# SCH_My-C51_2025-06-27.net
KiCad netlist of a schematic drawn in EasyEDA
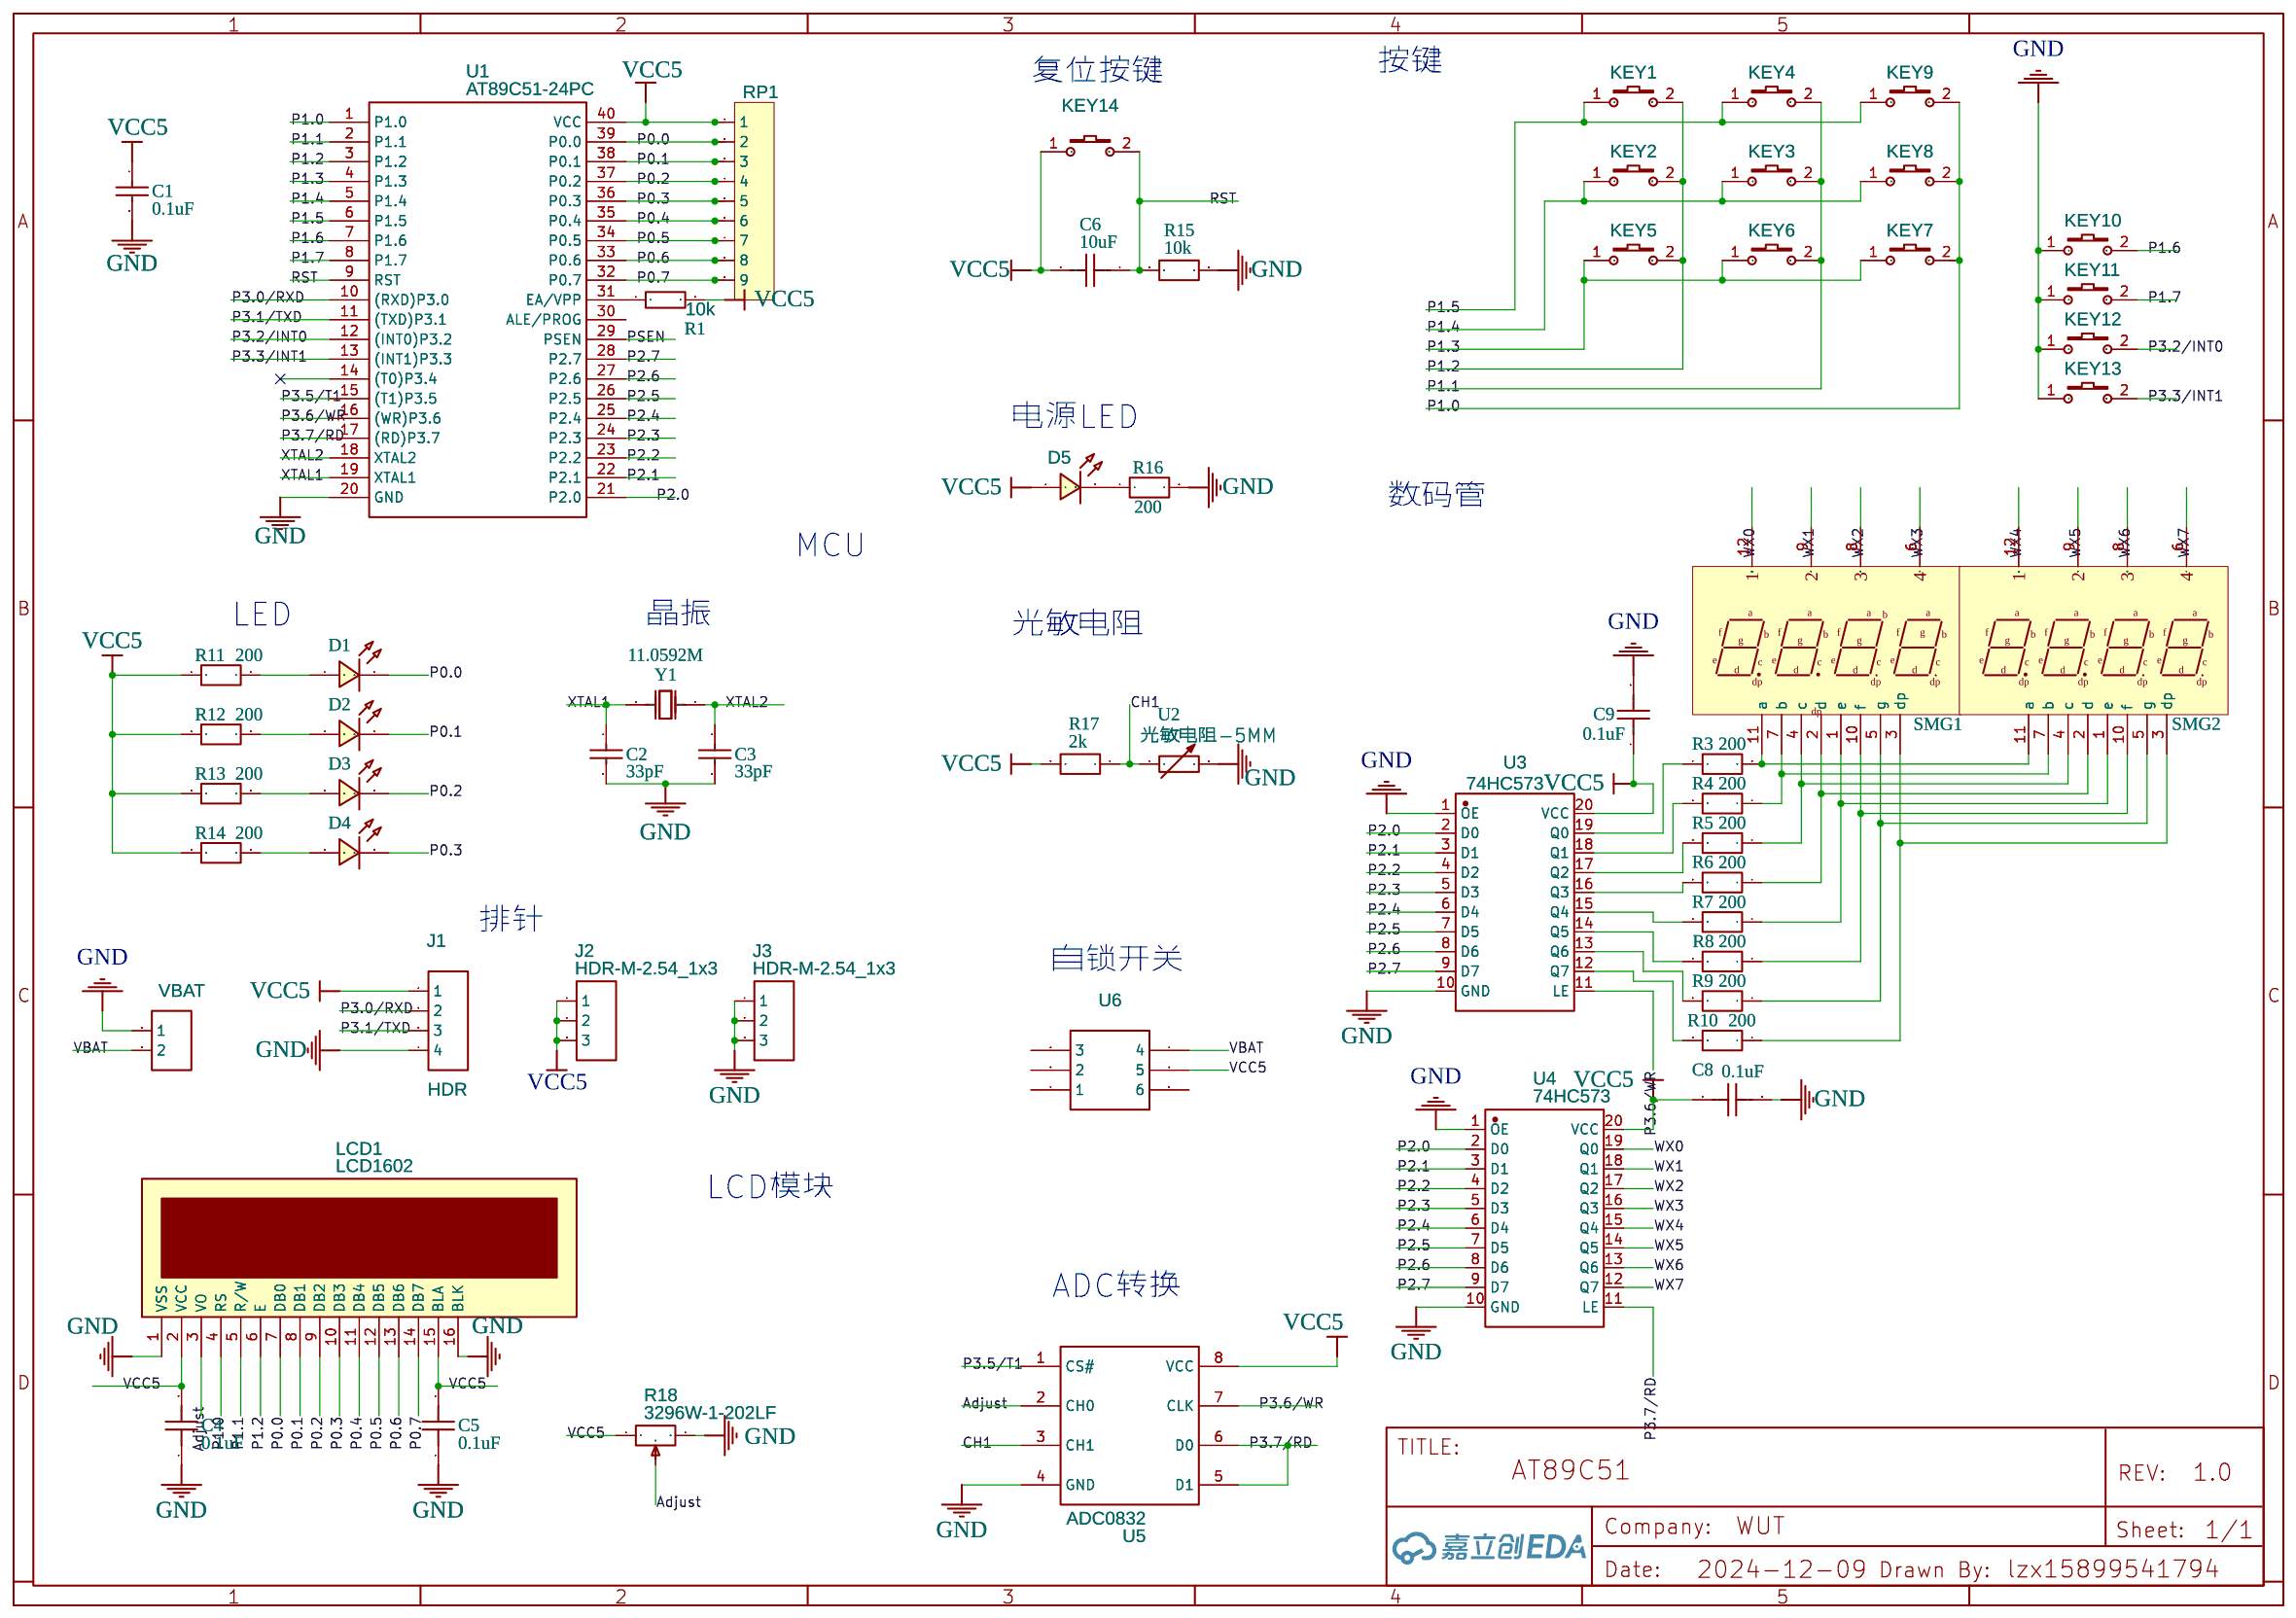
[diagram p0: schematic sheet]

(export (version "E")
  (design (tool "Eeschema 10.0.6"))
  (components
    (comp (ref "C1")
      (value "0.1uF")
      (fields
        (field (name "Manufacturer Part") "C0201X6S104K6R3NTA")
        (field (name "Manufacturer") "EYANG(宇阳科技)")
      )
      (libsource (lib "") (part "C0201X6S104K6R3NTA"))
    )
    (comp (ref "C2")
      (value "33pF")
      (fields (field (name "Manufacturer Part") "CGA2B2C0G1H330JT0Y0F") (field (name "Manufacturer") "TDK"))
      (libsource (lib "") (part "CGA2B2C0G1H330JT0Y0F"))
    )
    (comp (ref "C3")
      (value "33pF")
      (fields (field (name "Manufacturer Part") "CGA2B2C0G1H330JT0Y0F") (field (name "Manufacturer") "TDK"))
      (libsource (lib "") (part "CGA2B2C0G1H330JT0Y0F"))
    )
    (comp (ref "C4") (value "0.1uF") (libsource (lib "") (part "C_0603_US")))
    (comp (ref "C5") (value "0.1uF") (libsource (lib "") (part "C_0603_US")))
    (comp (ref "C6") (value "10uF") (libsource (lib "") (part "C_0603_US_1")))
    (comp (ref "C8") (value "0.1uF") (libsource (lib "") (part "C_0603_US_2")))
    (comp (ref "C9") (value "0.1uF") (libsource (lib "") (part "C_0603_US")))
    (comp (ref "D1")
      (value "LED-0603_R")
      (fields
        (field (name "Manufacturer Part") "19-217/R6C-AL1M2VY/3T")
        (field (name "Manufacturer") "EVERLIGHT(台湾亿光)")
      )
      (libsource (lib "") (part "LED-0603_R"))
    )
    (comp (ref "D2")
      (value "LED-0603_R")
      (fields
        (field (name "Manufacturer Part") "19-217/R6C-AL1M2VY/3T")
        (field (name "Manufacturer") "EVERLIGHT(台湾亿光)")
      )
      (libsource (lib "") (part "LED-0603_R"))
    )
    (comp (ref "D3")
      (value "LED-0603_R")
      (fields
        (field (name "Manufacturer Part") "19-217/R6C-AL1M2VY/3T")
        (field (name "Manufacturer") "EVERLIGHT(台湾亿光)")
      )
      (libsource (lib "") (part "LED-0603_R"))
    )
    (comp (ref "D4")
      (value "LED-0603_R")
      (fields
        (field (name "Manufacturer Part") "19-217/R6C-AL1M2VY/3T")
        (field (name "Manufacturer") "EVERLIGHT(台湾亿光)")
      )
      (libsource (lib "") (part "LED-0603_R"))
    )
    (comp (ref "D5")
      (value "LED-0603_R")
      (fields
        (field (name "Manufacturer Part") "19-217/R6C-AL1M2VY/3T")
        (field (name "Manufacturer") "EVERLIGHT(台湾亿光)")
      )
      (libsource (lib "") (part "LED-0603_R"))
    )
    (comp (ref "J1") (value "HDR") (libsource (lib "") (part "HDR-M-2.54_1x4")))
    (comp (ref "J2") (value "HDR-M-2.54_1x3") (libsource (lib "") (part "HDR-M-2.54_1x3")))
    (comp (ref "J3") (value "HDR-M-2.54_1x3") (libsource (lib "") (part "HDR-M-2.54_1x3")))
    (comp (ref "KEY1")
      (value "K2-3.6×6.1_SMD")
      (fields (field (name "Manufacturer Part") "K2-1107ST-A4SW-06"))
      (libsource (lib "") (part "K2-3.6×6.1_SMD"))
    )
    (comp (ref "KEY2")
      (value "K2-3.6×6.1_SMD")
      (fields (field (name "Manufacturer Part") "K2-1107ST-A4SW-06"))
      (libsource (lib "") (part "K2-3.6×6.1_SMD"))
    )
    (comp (ref "KEY3")
      (value "K2-3.6×6.1_SMD")
      (fields (field (name "Manufacturer Part") "K2-1107ST-A4SW-06"))
      (libsource (lib "") (part "K2-3.6×6.1_SMD"))
    )
    (comp (ref "KEY4")
      (value "K2-3.6×6.1_SMD")
      (fields (field (name "Manufacturer Part") "K2-1107ST-A4SW-06"))
      (libsource (lib "") (part "K2-3.6×6.1_SMD"))
    )
    (comp (ref "KEY5")
      (value "K2-3.6×6.1_SMD")
      (fields (field (name "Manufacturer Part") "K2-1107ST-A4SW-06"))
      (libsource (lib "") (part "K2-3.6×6.1_SMD"))
    )
    (comp (ref "KEY6")
      (value "K2-3.6×6.1_SMD")
      (fields (field (name "Manufacturer Part") "K2-1107ST-A4SW-06"))
      (libsource (lib "") (part "K2-3.6×6.1_SMD"))
    )
    (comp (ref "KEY7")
      (value "K2-3.6×6.1_SMD")
      (fields (field (name "Manufacturer Part") "K2-1107ST-A4SW-06"))
      (libsource (lib "") (part "K2-3.6×6.1_SMD"))
    )
    (comp (ref "KEY8")
      (value "K2-3.6×6.1_SMD")
      (fields (field (name "Manufacturer Part") "K2-1107ST-A4SW-06"))
      (libsource (lib "") (part "K2-3.6×6.1_SMD"))
    )
    (comp (ref "KEY9")
      (value "K2-3.6×6.1_SMD")
      (fields (field (name "Manufacturer Part") "K2-1107ST-A4SW-06"))
      (libsource (lib "") (part "K2-3.6×6.1_SMD"))
    )
    (comp (ref "KEY10")
      (value "K2-3.6×6.1_SMD")
      (fields (field (name "Manufacturer Part") "K2-1107ST-A4SW-06"))
      (libsource (lib "") (part "K2-3.6×6.1_SMD"))
    )
    (comp (ref "KEY11")
      (value "K2-3.6×6.1_SMD")
      (fields (field (name "Manufacturer Part") "K2-1107ST-A4SW-06"))
      (libsource (lib "") (part "K2-3.6×6.1_SMD"))
    )
    (comp (ref "KEY12")
      (value "K2-3.6×6.1_SMD")
      (fields (field (name "Manufacturer Part") "K2-1107ST-A4SW-06"))
      (libsource (lib "") (part "K2-3.6×6.1_SMD"))
    )
    (comp (ref "KEY13")
      (value "K2-3.6×6.1_SMD")
      (fields (field (name "Manufacturer Part") "K2-1107ST-A4SW-06"))
      (libsource (lib "") (part "K2-3.6×6.1_SMD"))
    )
    (comp (ref "KEY14")
      (value "K2-3.6×6.1_SMD")
      (fields (field (name "Manufacturer Part") "K2-1107ST-A4SW-06"))
      (libsource (lib "") (part "K2-3.6×6.1_SMD"))
    )
    (comp (ref "LCD1")
      (value "LCD1602")
      (fields
        (field (name "Manufacturer Part") "LCM1602K-NSW-BBW")
        (field (name "Manufacturer") "LONTECH(厦门龙特)")
      )
      (libsource (lib "") (part "LCD1602"))
    )
    (comp (ref "P11") (value "SMG2") (libsource (lib "") (part "0.36-4位数码管")))
    (comp (ref "P12") (value "SMG1") (libsource (lib "") (part "0.36-4位数码管_1")))
    (comp (ref "R1")
      (value "10k")
      (fields (field (name "Manufacturer Part") "RK73H1JTTD1052F") (field (name "Manufacturer") "KOA"))
      (libsource (lib "") (part "RK73H1JTTD1052F"))
    )
    (comp (ref "R3") (value "200") (libsource (lib "") (part "R_0603_EU")))
    (comp (ref "R4") (value "200") (libsource (lib "") (part "R_0603_EU_1")))
    (comp (ref "R5") (value "200") (libsource (lib "") (part "R_0603_EU_1")))
    (comp (ref "R6") (value "200") (libsource (lib "") (part "R_0603_EU_1")))
    (comp (ref "R7") (value "200") (libsource (lib "") (part "R_0603_EU_1")))
    (comp (ref "R8") (value "200") (libsource (lib "") (part "R_0603_EU_1")))
    (comp (ref "R9") (value "200") (libsource (lib "") (part "R_0603_EU_1")))
    (comp (ref "R10") (value "200") (libsource (lib "") (part "R_0603_EU_1")))
    (comp (ref "R11") (value "200") (libsource (lib "") (part "R_0603_EU")))
    (comp (ref "R12") (value "200") (libsource (lib "") (part "R_0603_EU")))
    (comp (ref "R13") (value "200") (libsource (lib "") (part "R_0603_EU")))
    (comp (ref "R14") (value "200") (libsource (lib "") (part "R_0603_EU")))
    (comp (ref "R15") (value "10k") (libsource (lib "") (part "R_0603_EU_1")))
    (comp (ref "R16") (value "200") (libsource (lib "") (part "R_0603_EU")))
    (comp (ref "R17") (value "2k") (libsource (lib "") (part "R_0603_EU_1")))
    (comp (ref "R18")
      (value "3296W-1-202LF")
      (fields (field (name "Manufacturer") "Bochen"))
      (libsource (lib "") (part "3296W-1-202LF_C118206 copy"))
    )
    (comp (ref "RP1") (value "排阻") (libsource (lib "") (part "排阻")))
    (comp (ref "U1") (value "AT89C51-24PC") (libsource (lib "") (part "AT89C51-24PC")))
    (comp (ref "U2") (value "光敏电阻-5MM") (libsource (lib "") (part "光敏电阻-5MM")))
    (comp (ref "U3")
      (value "74HC573")
      (fields
        (field (name "Manufacturer Part") "MC74HC573ADWR2G")
        (field (name "Manufacturer") "onsemi(安森美)")
      )
      (libsource (lib "") (part "74HC573"))
    )
    (comp (ref "U4")
      (value "74HC573")
      (fields
        (field (name "Manufacturer Part") "MC74HC573ADWR2G")
        (field (name "Manufacturer") "onsemi(安森美)")
      )
      (libsource (lib "") (part "74HC573"))
    )
    (comp (ref "U5") (value "ADC0832") (libsource (lib "") (part "ADC0832")))
    (comp (ref "U6") (value "自锁开关7*7") (libsource (lib "") (part "自锁开关7*7")))
    (comp (ref "VBAT") (value "端子") (libsource (lib "") (part "CONN-TH_2P-P5.00")))
    (comp (ref "Y1") (value "11.0592M") (libsource (lib "") (part "晶振")))
  )
  (nets
    (net (code "1") (name "/Adjust") (class "Default")
      (node (ref "LCD1") (pin "3") (pinfunction "VO_3") (pintype "unspecified"))
      (node (ref "R18") (pin "2") (pinfunction "2_2") (pintype "input"))
      (node (ref "U5") (pin "2") (pinfunction "CH0_2") (pintype "unspecified"))
    )
    (net (code "2") (name "/CH1") (class "Default")
      (node (ref "R17") (pin "1") (pinfunction "1_1") (pintype "unspecified"))
      (node (ref "U2") (pin "1") (pinfunction "1_1") (pintype "unspecified"))
      (node (ref "U5") (pin "3") (pinfunction "CH1_3") (pintype "unspecified"))
    )
    (net (code "3") (name "/P0.0") (class "Default")
      (node (ref "D1") (pin "2") (pinfunction "2_2") (pintype "unspecified"))
      (node (ref "LCD1") (pin "7") (pinfunction "DB0_7") (pintype "unspecified"))
      (node (ref "RP1") (pin "2") (pinfunction "2_2") (pintype "unspecified"))
      (node (ref "U1") (pin "39") (pinfunction "P0.0_39") (pintype "unspecified"))
    )
    (net (code "4") (name "/P0.1") (class "Default")
      (node (ref "D2") (pin "2") (pinfunction "2_2") (pintype "unspecified"))
      (node (ref "LCD1") (pin "8") (pinfunction "DB1_8") (pintype "unspecified"))
      (node (ref "RP1") (pin "3") (pinfunction "3_3") (pintype "unspecified"))
      (node (ref "U1") (pin "38") (pinfunction "P0.1_38") (pintype "unspecified"))
    )
    (net (code "5") (name "/P0.2") (class "Default")
      (node (ref "D3") (pin "2") (pinfunction "2_2") (pintype "unspecified"))
      (node (ref "LCD1") (pin "9") (pinfunction "DB2_9") (pintype "unspecified"))
      (node (ref "RP1") (pin "4") (pinfunction "4_4") (pintype "unspecified"))
      (node (ref "U1") (pin "37") (pinfunction "P0.2_37") (pintype "unspecified"))
    )
    (net (code "6") (name "/P0.3") (class "Default")
      (node (ref "D4") (pin "2") (pinfunction "2_2") (pintype "unspecified"))
      (node (ref "LCD1") (pin "10") (pinfunction "DB3_10") (pintype "unspecified"))
      (node (ref "RP1") (pin "5") (pinfunction "5_5") (pintype "unspecified"))
      (node (ref "U1") (pin "36") (pinfunction "P0.3_36") (pintype "unspecified"))
    )
    (net (code "7") (name "/P0.4") (class "Default")
      (node (ref "LCD1") (pin "11") (pinfunction "DB4_11") (pintype "unspecified"))
      (node (ref "RP1") (pin "6") (pinfunction "6_6") (pintype "unspecified"))
      (node (ref "U1") (pin "35") (pinfunction "P0.4_35") (pintype "unspecified"))
    )
    (net (code "8") (name "/P0.5") (class "Default")
      (node (ref "LCD1") (pin "12") (pinfunction "DB5_12") (pintype "unspecified"))
      (node (ref "RP1") (pin "7") (pinfunction "7_7") (pintype "unspecified"))
      (node (ref "U1") (pin "34") (pinfunction "P0.5_34") (pintype "unspecified"))
    )
    (net (code "9") (name "/P0.6") (class "Default")
      (node (ref "LCD1") (pin "13") (pinfunction "DB6_13") (pintype "unspecified"))
      (node (ref "RP1") (pin "8") (pinfunction "8_8") (pintype "unspecified"))
      (node (ref "U1") (pin "33") (pinfunction "P0.6_33") (pintype "unspecified"))
    )
    (net (code "10") (name "/P0.7") (class "Default")
      (node (ref "LCD1") (pin "14") (pinfunction "DB7_14") (pintype "unspecified"))
      (node (ref "RP1") (pin "9") (pinfunction "9_9") (pintype "unspecified"))
      (node (ref "U1") (pin "32") (pinfunction "P0.7_32") (pintype "unspecified"))
    )
    (net (code "11") (name "/P1.0") (class "Default")
      (node (ref "KEY7") (pin "2") (pinfunction "2_2") (pintype "unspecified"))
      (node (ref "KEY8") (pin "2") (pinfunction "2_2") (pintype "unspecified"))
      (node (ref "KEY9") (pin "2") (pinfunction "2_2") (pintype "unspecified"))
      (node (ref "LCD1") (pin "4") (pinfunction "RS_4") (pintype "unspecified"))
      (node (ref "U1") (pin "1") (pinfunction "P1.0_1") (pintype "unspecified"))
    )
    (net (code "12") (name "/P1.1") (class "Default")
      (node (ref "KEY3") (pin "2") (pinfunction "2_2") (pintype "unspecified"))
      (node (ref "KEY4") (pin "2") (pinfunction "2_2") (pintype "unspecified"))
      (node (ref "KEY6") (pin "2") (pinfunction "2_2") (pintype "unspecified"))
      (node (ref "LCD1") (pin "5") (pinfunction "R/W_5") (pintype "unspecified"))
      (node (ref "U1") (pin "2") (pinfunction "P1.1_2") (pintype "unspecified"))
    )
    (net (code "13") (name "/P1.2") (class "Default")
      (node (ref "KEY1") (pin "2") (pinfunction "2_2") (pintype "unspecified"))
      (node (ref "KEY2") (pin "2") (pinfunction "2_2") (pintype "unspecified"))
      (node (ref "KEY5") (pin "2") (pinfunction "2_2") (pintype "unspecified"))
      (node (ref "LCD1") (pin "6") (pinfunction "E_6") (pintype "unspecified"))
      (node (ref "U1") (pin "3") (pinfunction "P1.2_3") (pintype "unspecified"))
    )
    (net (code "14") (name "/P1.3") (class "Default")
      (node (ref "KEY5") (pin "1") (pinfunction "1_1") (pintype "unspecified"))
      (node (ref "KEY6") (pin "1") (pinfunction "1_1") (pintype "unspecified"))
      (node (ref "KEY7") (pin "1") (pinfunction "1_1") (pintype "unspecified"))
      (node (ref "U1") (pin "4") (pinfunction "P1.3_4") (pintype "unspecified"))
    )
    (net (code "15") (name "/P1.4") (class "Default")
      (node (ref "KEY2") (pin "1") (pinfunction "1_1") (pintype "unspecified"))
      (node (ref "KEY3") (pin "1") (pinfunction "1_1") (pintype "unspecified"))
      (node (ref "KEY8") (pin "1") (pinfunction "1_1") (pintype "unspecified"))
      (node (ref "U1") (pin "5") (pinfunction "P1.4_5") (pintype "unspecified"))
    )
    (net (code "16") (name "/P1.5") (class "Default")
      (node (ref "KEY1") (pin "1") (pinfunction "1_1") (pintype "unspecified"))
      (node (ref "KEY4") (pin "1") (pinfunction "1_1") (pintype "unspecified"))
      (node (ref "KEY9") (pin "1") (pinfunction "1_1") (pintype "unspecified"))
      (node (ref "U1") (pin "6") (pinfunction "P1.5_6") (pintype "unspecified"))
    )
    (net (code "17") (name "/P1.6") (class "Default")
      (node (ref "KEY10") (pin "2") (pinfunction "2_2") (pintype "unspecified"))
      (node (ref "U1") (pin "7") (pinfunction "P1.6_7") (pintype "unspecified"))
    )
    (net (code "18") (name "/P1.7") (class "Default")
      (node (ref "KEY11") (pin "2") (pinfunction "2_2") (pintype "unspecified"))
      (node (ref "U1") (pin "8") (pinfunction "P1.7_8") (pintype "unspecified"))
    )
    (net (code "19") (name "/P2.0") (class "Default")
      (node (ref "U1") (pin "21") (pinfunction "P2.0_21") (pintype "unspecified"))
      (node (ref "U3") (pin "2") (pinfunction "D0_2") (pintype "unspecified"))
      (node (ref "U4") (pin "2") (pinfunction "D0_2") (pintype "unspecified"))
    )
    (net (code "20") (name "/P2.1") (class "Default")
      (node (ref "U1") (pin "22") (pinfunction "P2.1_22") (pintype "unspecified"))
      (node (ref "U3") (pin "3") (pinfunction "D1_3") (pintype "unspecified"))
      (node (ref "U4") (pin "3") (pinfunction "D1_3") (pintype "unspecified"))
    )
    (net (code "21") (name "/P2.2") (class "Default")
      (node (ref "U1") (pin "23") (pinfunction "P2.2_23") (pintype "unspecified"))
      (node (ref "U3") (pin "4") (pinfunction "D2_4") (pintype "unspecified"))
      (node (ref "U4") (pin "4") (pinfunction "D2_4") (pintype "unspecified"))
    )
    (net (code "22") (name "/P2.3") (class "Default")
      (node (ref "U1") (pin "24") (pinfunction "P2.3_24") (pintype "unspecified"))
      (node (ref "U3") (pin "5") (pinfunction "D3_5") (pintype "unspecified"))
      (node (ref "U4") (pin "5") (pinfunction "D3_5") (pintype "unspecified"))
    )
    (net (code "23") (name "/P2.4") (class "Default")
      (node (ref "U1") (pin "25") (pinfunction "P2.4_25") (pintype "unspecified"))
      (node (ref "U3") (pin "6") (pinfunction "D4_6") (pintype "unspecified"))
      (node (ref "U4") (pin "6") (pinfunction "D4_6") (pintype "unspecified"))
    )
    (net (code "24") (name "/P2.5") (class "Default")
      (node (ref "U1") (pin "26") (pinfunction "P2.5_26") (pintype "unspecified"))
      (node (ref "U3") (pin "7") (pinfunction "D5_7") (pintype "unspecified"))
      (node (ref "U4") (pin "7") (pinfunction "D5_7") (pintype "unspecified"))
    )
    (net (code "25") (name "/P2.6") (class "Default")
      (node (ref "U1") (pin "27") (pinfunction "P2.6_27") (pintype "unspecified"))
      (node (ref "U3") (pin "8") (pinfunction "D6_8") (pintype "unspecified"))
      (node (ref "U4") (pin "8") (pinfunction "D6_8") (pintype "unspecified"))
    )
    (net (code "26") (name "/P2.7") (class "Default")
      (node (ref "U1") (pin "28") (pinfunction "P2.7_28") (pintype "unspecified"))
      (node (ref "U3") (pin "9") (pinfunction "D7_9") (pintype "unspecified"))
      (node (ref "U4") (pin "9") (pinfunction "D7_9") (pintype "unspecified"))
    )
    (net (code "27") (name "/P3.0{slash}RXD") (class "Default")
      (node (ref "J1") (pin "2") (pinfunction "2_2") (pintype "unspecified"))
      (node (ref "U1") (pin "10") (pinfunction "(RXD)P3.0_10") (pintype "unspecified"))
    )
    (net (code "28") (name "/P3.1{slash}TXD") (class "Default")
      (node (ref "J1") (pin "3") (pinfunction "3_3") (pintype "unspecified"))
      (node (ref "U1") (pin "11") (pinfunction "(TXD)P3.1_11") (pintype "unspecified"))
    )
    (net (code "29") (name "/P3.2{slash}INT0") (class "Default")
      (node (ref "KEY12") (pin "2") (pinfunction "2_2") (pintype "unspecified"))
      (node (ref "U1") (pin "12") (pinfunction "(INT0)P3.2_12") (pintype "unspecified"))
    )
    (net (code "30") (name "/P3.3{slash}INT1") (class "Default")
      (node (ref "KEY13") (pin "2") (pinfunction "2_2") (pintype "unspecified"))
      (node (ref "U1") (pin "13") (pinfunction "(INT1)P3.3_13") (pintype "unspecified"))
    )
    (net (code "31") (name "/P3.5{slash}T1") (class "Default")
      (node (ref "U1") (pin "15") (pinfunction "(T1)P3.5_15") (pintype "unspecified"))
      (node (ref "U5") (pin "1") (pinfunction "CS#_1") (pintype "unspecified"))
    )
    (net (code "32") (name "/P3.6{slash}WR") (class "Default")
      (node (ref "U1") (pin "16") (pinfunction "(WR)P3.6_16") (pintype "unspecified"))
      (node (ref "U3") (pin "11") (pinfunction "LE_11") (pintype "unspecified"))
      (node (ref "U5") (pin "7") (pinfunction "CLK_7") (pintype "unspecified"))
    )
    (net (code "33") (name "/P3.7{slash}RD") (class "Default")
      (node (ref "U1") (pin "17") (pinfunction "(RD)P3.7_17") (pintype "unspecified"))
      (node (ref "U4") (pin "11") (pinfunction "LE_11") (pintype "unspecified"))
      (node (ref "U5") (pin "5") (pinfunction "D1_5") (pintype "unspecified"))
      (node (ref "U5") (pin "6") (pinfunction "D0_6") (pintype "unspecified"))
    )
    (net (code "34") (name "/PSEN") (class "Default")
      (node (ref "U1") (pin "29") (pinfunction "PSEN_29") (pintype "unspecified"))
    )
    (net (code "35") (name "/RST") (class "Default")
      (node (ref "C6") (pin "1") (pinfunction "1_1") (pintype "unspecified"))
      (node (ref "KEY14") (pin "2") (pinfunction "2_2") (pintype "unspecified"))
      (node (ref "R15") (pin "2") (pinfunction "2_2") (pintype "unspecified"))
      (node (ref "U1") (pin "9") (pinfunction "RST_9") (pintype "unspecified"))
    )
    (net (code "36") (name "/VBAT") (class "Default")
      (node (ref "U6") (pin "4") (pinfunction "4_4") (pintype "unspecified"))
      (node (ref "VBAT") (pin "2") (pinfunction "2_2") (pintype "unspecified"))
    )
    (net (code "37") (name "/WX0") (class "Default")
      (node (ref "P12") (pin "12") (pinfunction "com_12") (pintype "unspecified"))
      (node (ref "U4") (pin "19") (pinfunction "Q0_19") (pintype "unspecified"))
    )
    (net (code "38") (name "/WX1") (class "Default")
      (node (ref "P12") (pin "9") (pinfunction "2_9") (pintype "unspecified"))
      (node (ref "U4") (pin "18") (pinfunction "Q1_18") (pintype "unspecified"))
    )
    (net (code "39") (name "/WX2") (class "Default")
      (node (ref "P12") (pin "8") (pinfunction "3_8") (pintype "unspecified"))
      (node (ref "U4") (pin "17") (pinfunction "Q2_17") (pintype "unspecified"))
    )
    (net (code "40") (name "/WX3") (class "Default")
      (node (ref "P12") (pin "6") (pinfunction "4_6") (pintype "unspecified"))
      (node (ref "U4") (pin "16") (pinfunction "Q3_16") (pintype "unspecified"))
    )
    (net (code "41") (name "/WX4") (class "Default")
      (node (ref "P11") (pin "12") (pinfunction "com_12") (pintype "unspecified"))
      (node (ref "U4") (pin "15") (pinfunction "Q4_15") (pintype "unspecified"))
    )
    (net (code "42") (name "/WX5") (class "Default")
      (node (ref "P11") (pin "9") (pinfunction "2_9") (pintype "unspecified"))
      (node (ref "U4") (pin "14") (pinfunction "Q5_14") (pintype "unspecified"))
    )
    (net (code "43") (name "/WX6") (class "Default")
      (node (ref "P11") (pin "8") (pinfunction "3_8") (pintype "unspecified"))
      (node (ref "U4") (pin "13") (pinfunction "Q6_13") (pintype "unspecified"))
    )
    (net (code "44") (name "/WX7") (class "Default")
      (node (ref "P11") (pin "6") (pinfunction "4_6") (pintype "unspecified"))
      (node (ref "U4") (pin "12") (pinfunction "Q7_12") (pintype "unspecified"))
    )
    (net (code "45") (name "/XTAL1") (class "Default")
      (node (ref "C2") (pin "1") (pinfunction "1_1") (pintype "input"))
      (node (ref "U1") (pin "19") (pinfunction "XTAL1_19") (pintype "unspecified"))
      (node (ref "Y1") (pin "2") (pinfunction "OSC2_2") (pintype "input"))
    )
    (net (code "46") (name "/XTAL2") (class "Default")
      (node (ref "C3") (pin "1") (pinfunction "1_1") (pintype "input"))
      (node (ref "U1") (pin "18") (pinfunction "XTAL2_18") (pintype "unspecified"))
      (node (ref "Y1") (pin "1") (pinfunction "OSC1_1") (pintype "input"))
    )
    (net (code "47") (name "GND") (class "Default")
      (node (ref "C1") (pin "2") (pinfunction "2_2") (pintype "input"))
      (node (ref "C2") (pin "2") (pinfunction "2_2") (pintype "input"))
      (node (ref "C3") (pin "2") (pinfunction "2_2") (pintype "input"))
      (node (ref "C4") (pin "1") (pinfunction "1_1") (pintype "unspecified"))
      (node (ref "C5") (pin "1") (pinfunction "1_1") (pintype "unspecified"))
      (node (ref "C8") (pin "2") (pinfunction "2_2") (pintype "unspecified"))
      (node (ref "C9") (pin "2") (pinfunction "2_2") (pintype "unspecified"))
      (node (ref "J1") (pin "4") (pinfunction "4_4") (pintype "unspecified"))
      (node (ref "J3") (pin "1") (pinfunction "1_1") (pintype "input"))
      (node (ref "J3") (pin "2") (pinfunction "2_2") (pintype "input"))
      (node (ref "J3") (pin "3") (pinfunction "3_3") (pintype "input"))
      (node (ref "KEY10") (pin "1") (pinfunction "1_1") (pintype "unspecified"))
      (node (ref "KEY11") (pin "1") (pinfunction "1_1") (pintype "unspecified"))
      (node (ref "KEY12") (pin "1") (pinfunction "1_1") (pintype "unspecified"))
      (node (ref "KEY13") (pin "1") (pinfunction "1_1") (pintype "unspecified"))
      (node (ref "LCD1") (pin "1") (pinfunction "VSS_1") (pintype "unspecified"))
      (node (ref "LCD1") (pin "16") (pinfunction "BLK_16") (pintype "unspecified"))
      (node (ref "R15") (pin "1") (pinfunction "1_1") (pintype "unspecified"))
      (node (ref "R16") (pin "2") (pinfunction "2_2") (pintype "unspecified"))
      (node (ref "R18") (pin "3") (pinfunction "3_3") (pintype "input"))
      (node (ref "U1") (pin "20") (pinfunction "GND_20") (pintype "unspecified"))
      (node (ref "U2") (pin "2") (pinfunction "2_2") (pintype "unspecified"))
      (node (ref "U3") (pin "1") (pinfunction "OE_1") (pintype "unspecified"))
      (node (ref "U3") (pin "10") (pinfunction "GND_10") (pintype "unspecified"))
      (node (ref "U4") (pin "1") (pinfunction "OE_1") (pintype "unspecified"))
      (node (ref "U4") (pin "10") (pinfunction "GND_10") (pintype "unspecified"))
      (node (ref "U5") (pin "4") (pinfunction "GND_4") (pintype "unspecified"))
      (node (ref "VBAT") (pin "1") (pinfunction "1_1") (pintype "unspecified"))
    )
    (net (code "48") (name "Net-(D1-Pad1)") (class "Default")
      (node (ref "D1") (pin "1") (pinfunction "1_1") (pintype "unspecified"))
      (node (ref "R11") (pin "2") (pinfunction "2_2") (pintype "unspecified"))
    )
    (net (code "49") (name "Net-(D2-Pad1)") (class "Default")
      (node (ref "D2") (pin "1") (pinfunction "1_1") (pintype "unspecified"))
      (node (ref "R12") (pin "2") (pinfunction "2_2") (pintype "unspecified"))
    )
    (net (code "50") (name "Net-(D3-Pad1)") (class "Default")
      (node (ref "D3") (pin "1") (pinfunction "1_1") (pintype "unspecified"))
      (node (ref "R13") (pin "2") (pinfunction "2_2") (pintype "unspecified"))
    )
    (net (code "51") (name "Net-(D4-Pad1)") (class "Default")
      (node (ref "D4") (pin "1") (pinfunction "1_1") (pintype "unspecified"))
      (node (ref "R14") (pin "2") (pinfunction "2_2") (pintype "unspecified"))
    )
    (net (code "52") (name "Net-(D5-Pad2)") (class "Default")
      (node (ref "D5") (pin "2") (pinfunction "2_2") (pintype "unspecified"))
      (node (ref "R16") (pin "1") (pinfunction "1_1") (pintype "unspecified"))
    )
    (net (code "53") (name "Net-(P11-a)") (class "Default")
      (node (ref "P11") (pin "11") (pinfunction "a_11") (pintype "unspecified"))
      (node (ref "P12") (pin "11") (pinfunction "a_11") (pintype "unspecified"))
      (node (ref "R3") (pin "2") (pinfunction "2_2") (pintype "unspecified"))
    )
    (net (code "54") (name "Net-(P11-b)") (class "Default")
      (node (ref "P11") (pin "7") (pinfunction "b_7") (pintype "unspecified"))
      (node (ref "P12") (pin "7") (pinfunction "b_7") (pintype "unspecified"))
      (node (ref "R4") (pin "1") (pinfunction "1_1") (pintype "unspecified"))
    )
    (net (code "55") (name "Net-(P11-c)") (class "Default")
      (node (ref "P11") (pin "4") (pinfunction "c_4") (pintype "unspecified"))
      (node (ref "P12") (pin "4") (pinfunction "c_4") (pintype "unspecified"))
      (node (ref "R5") (pin "1") (pinfunction "1_1") (pintype "unspecified"))
    )
    (net (code "56") (name "Net-(P11-d)") (class "Default")
      (node (ref "P11") (pin "2") (pinfunction "d_2") (pintype "unspecified"))
      (node (ref "P12") (pin "2") (pinfunction "d_2") (pintype "unspecified"))
      (node (ref "R6") (pin "1") (pinfunction "1_1") (pintype "unspecified"))
    )
    (net (code "57") (name "Net-(P11-dp)") (class "Default")
      (node (ref "P11") (pin "3") (pinfunction "dp_3") (pintype "unspecified"))
      (node (ref "P12") (pin "3") (pinfunction "dp_3") (pintype "unspecified"))
      (node (ref "R10") (pin "1") (pinfunction "1_1") (pintype "unspecified"))
    )
    (net (code "58") (name "Net-(P11-e)") (class "Default")
      (node (ref "P11") (pin "1") (pinfunction "e_1") (pintype "unspecified"))
      (node (ref "P12") (pin "1") (pinfunction "e_1") (pintype "unspecified"))
      (node (ref "R7") (pin "1") (pinfunction "1_1") (pintype "unspecified"))
    )
    (net (code "59") (name "Net-(P11-f)") (class "Default")
      (node (ref "P11") (pin "10") (pinfunction "f_10") (pintype "unspecified"))
      (node (ref "P12") (pin "10") (pinfunction "f_10") (pintype "unspecified"))
      (node (ref "R8") (pin "1") (pinfunction "1_1") (pintype "unspecified"))
    )
    (net (code "60") (name "Net-(P11-g)") (class "Default")
      (node (ref "P11") (pin "5") (pinfunction "g_5") (pintype "unspecified"))
      (node (ref "P12") (pin "5") (pinfunction "g_5") (pintype "unspecified"))
      (node (ref "R9") (pin "1") (pinfunction "1_1") (pintype "unspecified"))
    )
    (net (code "61") (name "Net-(U1-EA{slash}VPP)") (class "Default")
      (node (ref "R1") (pin "1") (pinfunction "1_1") (pintype "unspecified"))
      (node (ref "U1") (pin "31") (pinfunction "EA/VPP_31") (pintype "unspecified"))
    )
    (net (code "62") (name "Net-(U3-Q0)") (class "Default")
      (node (ref "R3") (pin "1") (pinfunction "1_1") (pintype "unspecified"))
      (node (ref "U3") (pin "19") (pinfunction "Q0_19") (pintype "unspecified"))
    )
    (net (code "63") (name "Net-(U3-Q1)") (class "Default")
      (node (ref "R4") (pin "2") (pinfunction "2_2") (pintype "unspecified"))
      (node (ref "U3") (pin "18") (pinfunction "Q1_18") (pintype "unspecified"))
    )
    (net (code "64") (name "Net-(U3-Q2)") (class "Default")
      (node (ref "R5") (pin "2") (pinfunction "2_2") (pintype "unspecified"))
      (node (ref "U3") (pin "17") (pinfunction "Q2_17") (pintype "unspecified"))
    )
    (net (code "65") (name "Net-(U3-Q3)") (class "Default")
      (node (ref "R6") (pin "2") (pinfunction "2_2") (pintype "unspecified"))
      (node (ref "U3") (pin "16") (pinfunction "Q3_16") (pintype "unspecified"))
    )
    (net (code "66") (name "Net-(U3-Q4)") (class "Default")
      (node (ref "R7") (pin "2") (pinfunction "2_2") (pintype "unspecified"))
      (node (ref "U3") (pin "15") (pinfunction "Q4_15") (pintype "unspecified"))
    )
    (net (code "67") (name "Net-(U3-Q5)") (class "Default")
      (node (ref "R8") (pin "2") (pinfunction "2_2") (pintype "unspecified"))
      (node (ref "U3") (pin "14") (pinfunction "Q5_14") (pintype "unspecified"))
    )
    (net (code "68") (name "Net-(U3-Q6)") (class "Default")
      (node (ref "R9") (pin "2") (pinfunction "2_2") (pintype "unspecified"))
      (node (ref "U3") (pin "13") (pinfunction "Q6_13") (pintype "unspecified"))
    )
    (net (code "69") (name "Net-(U3-Q7)") (class "Default")
      (node (ref "R10") (pin "2") (pinfunction "2_2") (pintype "unspecified"))
      (node (ref "U3") (pin "12") (pinfunction "Q7_12") (pintype "unspecified"))
    )
    (net (code "70") (name "VCC5") (class "Default")
      (node (ref "C1") (pin "1") (pinfunction "1_1") (pintype "input"))
      (node (ref "C4") (pin "2") (pinfunction "2_2") (pintype "unspecified"))
      (node (ref "C5") (pin "2") (pinfunction "2_2") (pintype "unspecified"))
      (node (ref "C6") (pin "2") (pinfunction "2_2") (pintype "unspecified"))
      (node (ref "C8") (pin "1") (pinfunction "1_1") (pintype "unspecified"))
      (node (ref "C9") (pin "1") (pinfunction "1_1") (pintype "unspecified"))
      (node (ref "D5") (pin "1") (pinfunction "1_1") (pintype "unspecified"))
      (node (ref "J1") (pin "1") (pinfunction "1_1") (pintype "unspecified"))
      (node (ref "J2") (pin "1") (pinfunction "1_1") (pintype "input"))
      (node (ref "J2") (pin "2") (pinfunction "2_2") (pintype "input"))
      (node (ref "J2") (pin "3") (pinfunction "3_3") (pintype "input"))
      (node (ref "KEY14") (pin "1") (pinfunction "1_1") (pintype "unspecified"))
      (node (ref "LCD1") (pin "15") (pinfunction "BLA_15") (pintype "unspecified"))
      (node (ref "LCD1") (pin "2") (pinfunction "VCC_2") (pintype "unspecified"))
      (node (ref "R1") (pin "2") (pinfunction "2_2") (pintype "unspecified"))
      (node (ref "R11") (pin "1") (pinfunction "1_1") (pintype "unspecified"))
      (node (ref "R12") (pin "1") (pinfunction "1_1") (pintype "unspecified"))
      (node (ref "R13") (pin "1") (pinfunction "1_1") (pintype "unspecified"))
      (node (ref "R14") (pin "1") (pinfunction "1_1") (pintype "unspecified"))
      (node (ref "R17") (pin "2") (pinfunction "2_2") (pintype "unspecified"))
      (node (ref "R18") (pin "1") (pinfunction "1_1") (pintype "input"))
      (node (ref "RP1") (pin "1") (pinfunction "1_1") (pintype "unspecified"))
      (node (ref "U1") (pin "40") (pinfunction "VCC_40") (pintype "unspecified"))
      (node (ref "U3") (pin "20") (pinfunction "VCC_20") (pintype "unspecified"))
      (node (ref "U4") (pin "20") (pinfunction "VCC_20") (pintype "unspecified"))
      (node (ref "U5") (pin "8") (pinfunction "VCC_8") (pintype "unspecified"))
      (node (ref "U6") (pin "5") (pinfunction "5_5") (pintype "unspecified"))
    )
    (net (code "71") (name "unconnected-(U1-(T0)P3.4-Pad14)") (class "Default")
      (node (ref "U1") (pin "14") (pinfunction "(T0)P3.4_14") (pintype "unspecified+no_connect"))
    )
    (net (code "72") (name "unconnected-(U1-ALE{slash}PROG-Pad30)") (class "Default")
      (node (ref "U1") (pin "30") (pinfunction "ALE/PROG_30") (pintype "unspecified"))
    )
    (net (code "73") (name "unconnected-(U6-Pad1)") (class "Default")
      (node (ref "U6") (pin "1") (pinfunction "1_1") (pintype "unspecified"))
    )
    (net (code "74") (name "unconnected-(U6-Pad2)") (class "Default")
      (node (ref "U6") (pin "2") (pinfunction "2_2") (pintype "unspecified"))
    )
    (net (code "75") (name "unconnected-(U6-Pad3)") (class "Default")
      (node (ref "U6") (pin "3") (pinfunction "3_3") (pintype "unspecified"))
    )
    (net (code "76") (name "unconnected-(U6-Pad6)") (class "Default")
      (node (ref "U6") (pin "6") (pinfunction "6_6") (pintype "unspecified"))
    )
  )
)
